# SCH_RoboFootball.net
KiCad netlist of a schematic drawn in EasyEDA
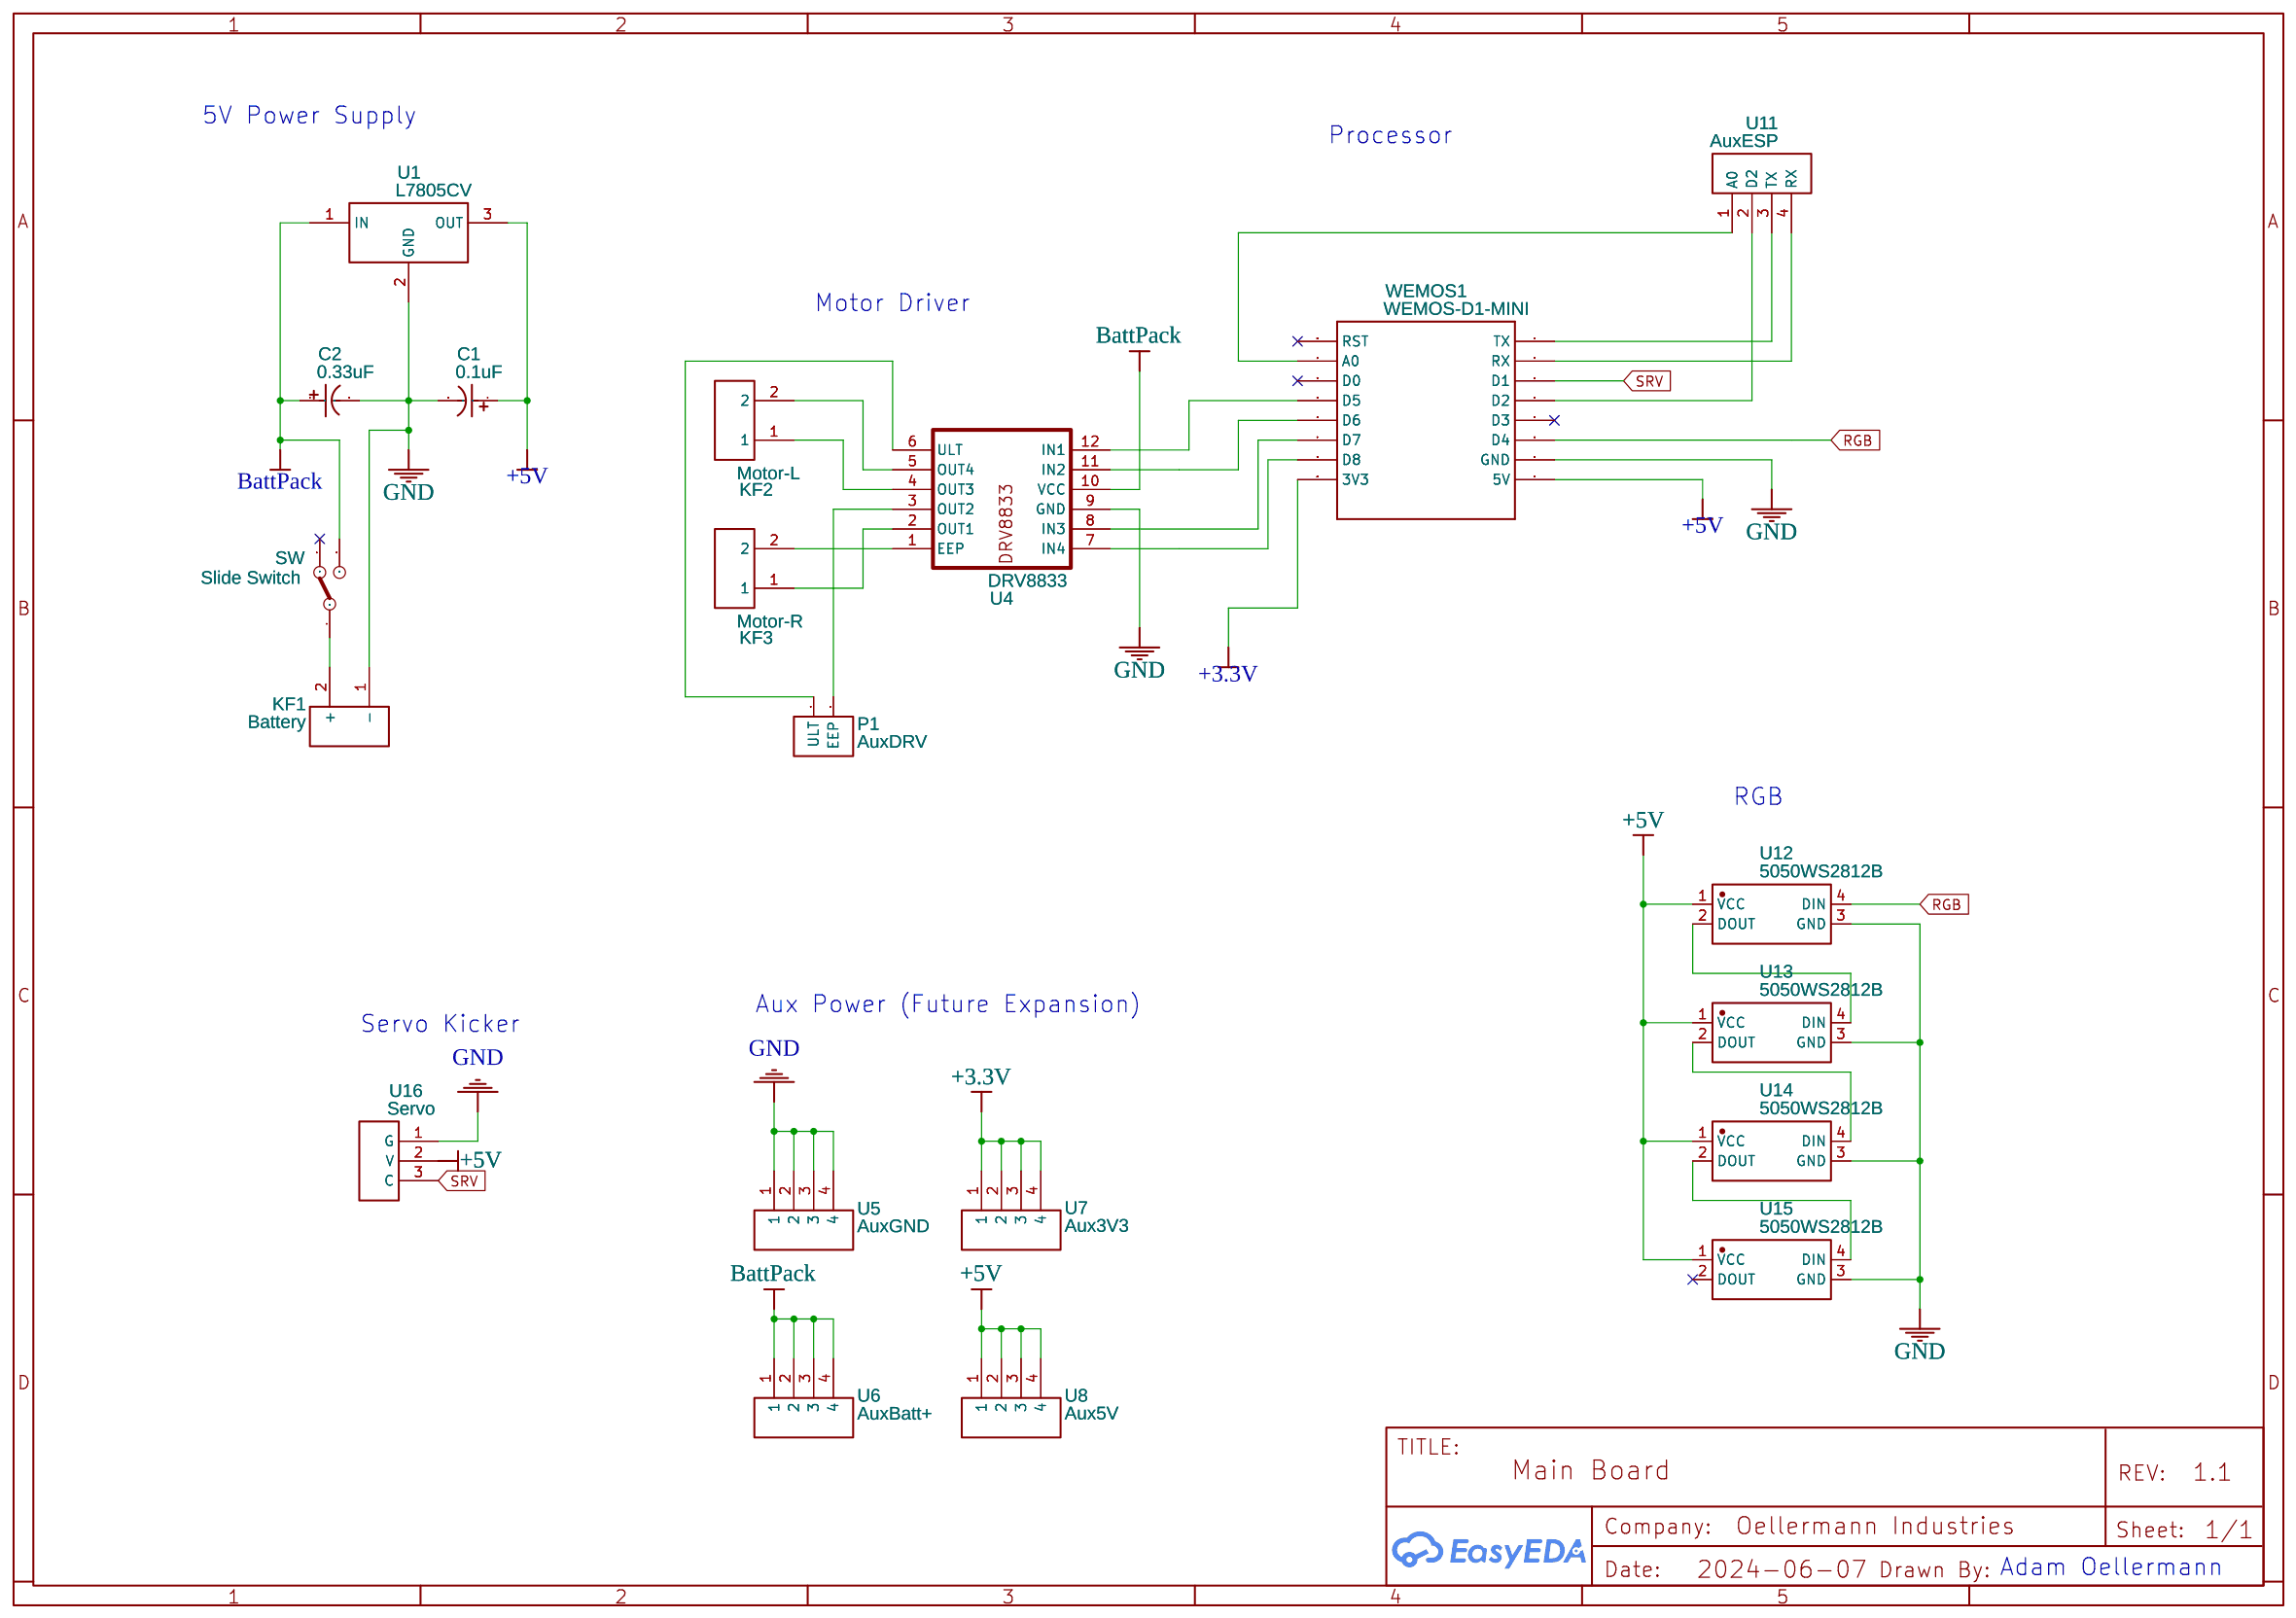
[diagram p0: schematic sheet]

(export (version "E")
  (design (tool "Eeschema 10.0.6"))
  (components
    (comp (ref "C1")
      (value "0.1uF")
      (fields
        (field (name "BOM_Manufacturer Part") "0.1uF 50V 4*7")
        (field (name "BOM_Supplier Part") "C45664")
      )
      (libsource (lib "") (part "0.1uF 50V 4*7"))
    )
    (comp (ref "C2")
      (value "0.33uF")
      (fields
        (field (name "BOM_Manufacturer Part") "0.33uF 50V 4*7")
        (field (name "BOM_Supplier Part") "C47875")
      )
      (libsource (lib "") (part "0.33uF 50V 4*7"))
    )
    (comp (ref "KF1") (value "Battery") (libsource (lib "") (part "K-301-2P_1")))
    (comp (ref "KF2") (value "Motor-L") (libsource (lib "") (part "K-301-2P")))
    (comp (ref "KF3") (value "Motor-R") (libsource (lib "") (part "K-301-2P")))
    (comp (ref "P1")
      (value "AuxDRV")
      (fields
        (field (name "BOM_Manufacturer Part") "2.54-1*2PFemale")
        (field (name "BOM_Supplier Part") "C49661")
      )
      (libsource (lib "") (part "Header-Female-2.54_1x2"))
    )
    (comp (ref "SW")
      (value "Slide Switch")
      (fields (field (name "BOM_Manufacturer Part") "Switch SPDT"))
      (libsource (lib "") (part "Slide Switch"))
    )
    (comp (ref "U1")
      (value "L7805CV")
      (fields (field (name "BOM_Supplier Part") "C111887"))
      (libsource (lib "") (part "L7805CV"))
    )
    (comp (ref "U4") (value "DRV8833") (libsource (lib "") (part "DRV8833 (NO ORIGINAL)")))
    (comp (ref "U5")
      (value "AuxGND")
      (fields (field (name "BOM_Supplier Part") "undefined"))
      (libsource (lib "") (part "PINHEADER1X4_1"))
    )
    (comp (ref "U6")
      (value "AuxBatt+")
      (fields (field (name "BOM_Supplier Part") "undefined"))
      (libsource (lib "") (part "PINHEADER1X4_1"))
    )
    (comp (ref "U7")
      (value "Aux3V3")
      (fields (field (name "BOM_Supplier Part") "undefined"))
      (libsource (lib "") (part "PINHEADER1X4_1"))
    )
    (comp (ref "U8")
      (value "Aux5V")
      (fields (field (name "BOM_Supplier Part") "undefined"))
      (libsource (lib "") (part "PINHEADER1X4_1"))
    )
    (comp (ref "U11")
      (value "AuxESP")
      (fields (field (name "BOM_Supplier Part") "undefined"))
      (libsource (lib "") (part "PINHEADER1X4"))
    )
    (comp (ref "U12")
      (value "5050WS2812B")
      (fields (field (name "BOM_Supplier Part") "C2874876"))
      (libsource (lib "") (part "5050WS2812B"))
    )
    (comp (ref "U13")
      (value "5050WS2812B")
      (fields (field (name "BOM_Supplier Part") "C2874876"))
      (libsource (lib "") (part "5050WS2812B"))
    )
    (comp (ref "U14")
      (value "5050WS2812B")
      (fields (field (name "BOM_Supplier Part") "C2874876"))
      (libsource (lib "") (part "5050WS2812B"))
    )
    (comp (ref "U15")
      (value "5050WS2812B")
      (fields (field (name "BOM_Supplier Part") "C2874876"))
      (libsource (lib "") (part "5050WS2812B"))
    )
    (comp (ref "U16")
      (value "Servo")
      (fields (field (name "BOM_Manufacturer Part") "Pin_Header_2"))
      (libsource (lib "") (part "PINHEADER1X3"))
    )
    (comp (ref "WEMOS1") (value "WEMOS-D1-MINI") (libsource (lib "") (part "WEMOS-D1-MINI")))
  )
  (nets
    (net (code "1") (name "+3.3V") (class "Default")
      (node (ref "U7") (pin "1") (pinfunction "1_1") (pintype "unspecified"))
      (node (ref "U7") (pin "2") (pinfunction "2_2") (pintype "unspecified"))
      (node (ref "U7") (pin "3") (pinfunction "3_3") (pintype "unspecified"))
      (node (ref "U7") (pin "4") (pinfunction "4_4") (pintype "unspecified"))
      (node (ref "WEMOS1") (pin "3V3") (pinfunction "3V3_3V3") (pintype "unspecified"))
    )
    (net (code "2") (name "+5V") (class "Default")
      (node (ref "C1") (pin "1") (pinfunction "1_1") (pintype "input"))
      (node (ref "U1") (pin "3") (pinfunction "OUT_3") (pintype "passive"))
      (node (ref "U12") (pin "1") (pinfunction "VCC_1") (pintype "unspecified"))
      (node (ref "U13") (pin "1") (pinfunction "VCC_1") (pintype "unspecified"))
      (node (ref "U14") (pin "1") (pinfunction "VCC_1") (pintype "unspecified"))
      (node (ref "U15") (pin "1") (pinfunction "VCC_1") (pintype "unspecified"))
      (node (ref "U16") (pin "2") (pinfunction "V_2") (pintype "unspecified"))
      (node (ref "U8") (pin "1") (pinfunction "1_1") (pintype "unspecified"))
      (node (ref "U8") (pin "2") (pinfunction "2_2") (pintype "unspecified"))
      (node (ref "U8") (pin "3") (pinfunction "3_3") (pintype "unspecified"))
      (node (ref "U8") (pin "4") (pinfunction "4_4") (pintype "unspecified"))
      (node (ref "WEMOS1") (pin "5V") (pinfunction "5V_5V") (pintype "unspecified"))
    )
    (net (code "3") (name "BattPack") (class "Default")
      (node (ref "C2") (pin "1") (pinfunction "1_1") (pintype "input"))
      (node (ref "SW") (pin "3") (pinfunction "NO_3") (pintype "unspecified"))
      (node (ref "U1") (pin "1") (pinfunction "IN_1") (pintype "passive"))
      (node (ref "U4") (pin "10") (pinfunction "VCC_10") (pintype "unspecified"))
      (node (ref "U6") (pin "1") (pinfunction "1_1") (pintype "unspecified"))
      (node (ref "U6") (pin "2") (pinfunction "2_2") (pintype "unspecified"))
      (node (ref "U6") (pin "3") (pinfunction "3_3") (pintype "unspecified"))
      (node (ref "U6") (pin "4") (pinfunction "4_4") (pintype "unspecified"))
    )
    (net (code "4") (name "GND") (class "Default")
      (node (ref "C1") (pin "2") (pinfunction "2_2") (pintype "input"))
      (node (ref "C2") (pin "2") (pinfunction "2_2") (pintype "input"))
      (node (ref "KF1") (pin "1") (pinfunction "-_1") (pintype "unspecified"))
      (node (ref "U1") (pin "2") (pinfunction "GND_2") (pintype "passive"))
      (node (ref "U12") (pin "3") (pinfunction "GND_3") (pintype "unspecified"))
      (node (ref "U13") (pin "3") (pinfunction "GND_3") (pintype "unspecified"))
      (node (ref "U14") (pin "3") (pinfunction "GND_3") (pintype "unspecified"))
      (node (ref "U15") (pin "3") (pinfunction "GND_3") (pintype "unspecified"))
      (node (ref "U16") (pin "1") (pinfunction "G_1") (pintype "unspecified"))
      (node (ref "U4") (pin "9") (pinfunction "GND_9") (pintype "unspecified"))
      (node (ref "U5") (pin "1") (pinfunction "1_1") (pintype "unspecified"))
      (node (ref "U5") (pin "2") (pinfunction "2_2") (pintype "unspecified"))
      (node (ref "U5") (pin "3") (pinfunction "3_3") (pintype "unspecified"))
      (node (ref "U5") (pin "4") (pinfunction "4_4") (pintype "unspecified"))
      (node (ref "WEMOS1") (pin "GND") (pinfunction "GND_GND") (pintype "unspecified"))
    )
    (net (code "5") (name "Net-(KF1-+)") (class "Default")
      (node (ref "KF1") (pin "2") (pinfunction "+_2") (pintype "unspecified"))
      (node (ref "SW") (pin "1") (pinfunction "NC_1") (pintype "unspecified"))
    )
    (net (code "6") (name "Net-(P1-EEP)") (class "Default")
      (node (ref "KF3") (pin "2") (pinfunction "2_2") (pintype "unspecified"))
      (node (ref "P1") (pin "1") (pinfunction "EEP_1") (pintype "input"))
      (node (ref "U4") (pin "1") (pinfunction "EEP_1") (pintype "unspecified"))
      (node (ref "U4") (pin "3") (pinfunction "OUT2_3") (pintype "unspecified"))
    )
    (net (code "7") (name "Net-(P1-ULT)") (class "Default")
      (node (ref "P1") (pin "2") (pinfunction "ULT_2") (pintype "input"))
      (node (ref "U4") (pin "6") (pinfunction "ULT_6") (pintype "unspecified"))
    )
    (net (code "8") (name "Net-(U4-IN1)") (class "Default")
      (node (ref "U4") (pin "12") (pinfunction "IN1_12") (pintype "unspecified"))
      (node (ref "WEMOS1") (pin "D5") (pinfunction "D5_D5") (pintype "unspecified"))
    )
    (net (code "9") (name "Net-(U4-IN2)") (class "Default")
      (node (ref "U4") (pin "11") (pinfunction "IN2_11") (pintype "unspecified"))
      (node (ref "WEMOS1") (pin "D6") (pinfunction "D6_D6") (pintype "unspecified"))
    )
    (net (code "10") (name "Net-(U4-IN3)") (class "Default")
      (node (ref "U4") (pin "8") (pinfunction "IN3_8") (pintype "unspecified"))
      (node (ref "WEMOS1") (pin "D7") (pinfunction "D7_D7") (pintype "unspecified"))
    )
    (net (code "11") (name "Net-(U4-IN4)") (class "Default")
      (node (ref "U4") (pin "7") (pinfunction "IN4_7") (pintype "unspecified"))
      (node (ref "WEMOS1") (pin "D8") (pinfunction "D8_D8") (pintype "unspecified"))
    )
    (net (code "12") (name "Net-(U4-OUT1)") (class "Default")
      (node (ref "KF3") (pin "1") (pinfunction "1_1") (pintype "unspecified"))
      (node (ref "U4") (pin "2") (pinfunction "OUT1_2") (pintype "unspecified"))
    )
    (net (code "13") (name "Net-(U4-OUT3)") (class "Default")
      (node (ref "KF2") (pin "1") (pinfunction "1_1") (pintype "unspecified"))
      (node (ref "U4") (pin "4") (pinfunction "OUT3_4") (pintype "unspecified"))
    )
    (net (code "14") (name "Net-(U4-OUT4)") (class "Default")
      (node (ref "KF2") (pin "2") (pinfunction "2_2") (pintype "unspecified"))
      (node (ref "U4") (pin "5") (pinfunction "OUT4_5") (pintype "unspecified"))
    )
    (net (code "15") (name "Net-(U11-A0)") (class "Default")
      (node (ref "U11") (pin "1") (pinfunction "A0_1") (pintype "unspecified"))
      (node (ref "WEMOS1") (pin "A0") (pinfunction "A0_A0") (pintype "unspecified"))
    )
    (net (code "16") (name "Net-(U11-D2)") (class "Default")
      (node (ref "U11") (pin "2") (pinfunction "D2_2") (pintype "unspecified"))
      (node (ref "WEMOS1") (pin "D2") (pinfunction "D2_D2") (pintype "unspecified"))
    )
    (net (code "17") (name "Net-(U11-RX)") (class "Default")
      (node (ref "U11") (pin "4") (pinfunction "RX_4") (pintype "unspecified"))
      (node (ref "WEMOS1") (pin "RX") (pinfunction "RX_RX") (pintype "unspecified"))
    )
    (net (code "18") (name "Net-(U11-TX)") (class "Default")
      (node (ref "U11") (pin "3") (pinfunction "TX_3") (pintype "unspecified"))
      (node (ref "WEMOS1") (pin "TX") (pinfunction "TX_TX") (pintype "unspecified"))
    )
    (net (code "19") (name "Net-(U12-DOUT)") (class "Default")
      (node (ref "U12") (pin "2") (pinfunction "DOUT_2") (pintype "unspecified"))
      (node (ref "U13") (pin "4") (pinfunction "DIN_4") (pintype "unspecified"))
    )
    (net (code "20") (name "Net-(U13-DOUT)") (class "Default")
      (node (ref "U13") (pin "2") (pinfunction "DOUT_2") (pintype "unspecified"))
      (node (ref "U14") (pin "4") (pinfunction "DIN_4") (pintype "unspecified"))
    )
    (net (code "21") (name "Net-(U14-DOUT)") (class "Default")
      (node (ref "U14") (pin "2") (pinfunction "DOUT_2") (pintype "unspecified"))
      (node (ref "U15") (pin "4") (pinfunction "DIN_4") (pintype "unspecified"))
    )
    (net (code "22") (name "RGB") (class "Default")
      (node (ref "U12") (pin "4") (pinfunction "DIN_4") (pintype "unspecified"))
      (node (ref "WEMOS1") (pin "D4") (pinfunction "D4_D4") (pintype "unspecified"))
    )
    (net (code "23") (name "SRV") (class "Default")
      (node (ref "U16") (pin "3") (pinfunction "C_3") (pintype "unspecified"))
      (node (ref "WEMOS1") (pin "D1") (pinfunction "D1_D1") (pintype "unspecified"))
    )
    (net (code "24") (name "unconnected-(SW-C-Pad2)") (class "Default")
      (node (ref "SW") (pin "2") (pinfunction "C_2") (pintype "unspecified+no_connect"))
    )
    (net (code "25") (name "unconnected-(U15-DOUT-Pad2)") (class "Default")
      (node (ref "U15") (pin "2") (pinfunction "DOUT_2") (pintype "unspecified+no_connect"))
    )
    (net (code "26") (name "unconnected-(WEMOS1-PadD0)") (class "Default")
      (node (ref "WEMOS1") (pin "D0") (pinfunction "D0_D0") (pintype "unspecified+no_connect"))
    )
    (net (code "27") (name "unconnected-(WEMOS1-PadD3)") (class "Default")
      (node (ref "WEMOS1") (pin "D3") (pinfunction "D3_D3") (pintype "unspecified+no_connect"))
    )
    (net (code "28") (name "unconnected-(WEMOS1-PadRST)") (class "Default")
      (node (ref "WEMOS1") (pin "RST") (pinfunction "RST_RST") (pintype "unspecified+no_connect"))
    )
  )
)
